# QCLogic_Rev_A_Sht2_WiFi.net
KiCad netlist of a schematic drawn in Altium Designer
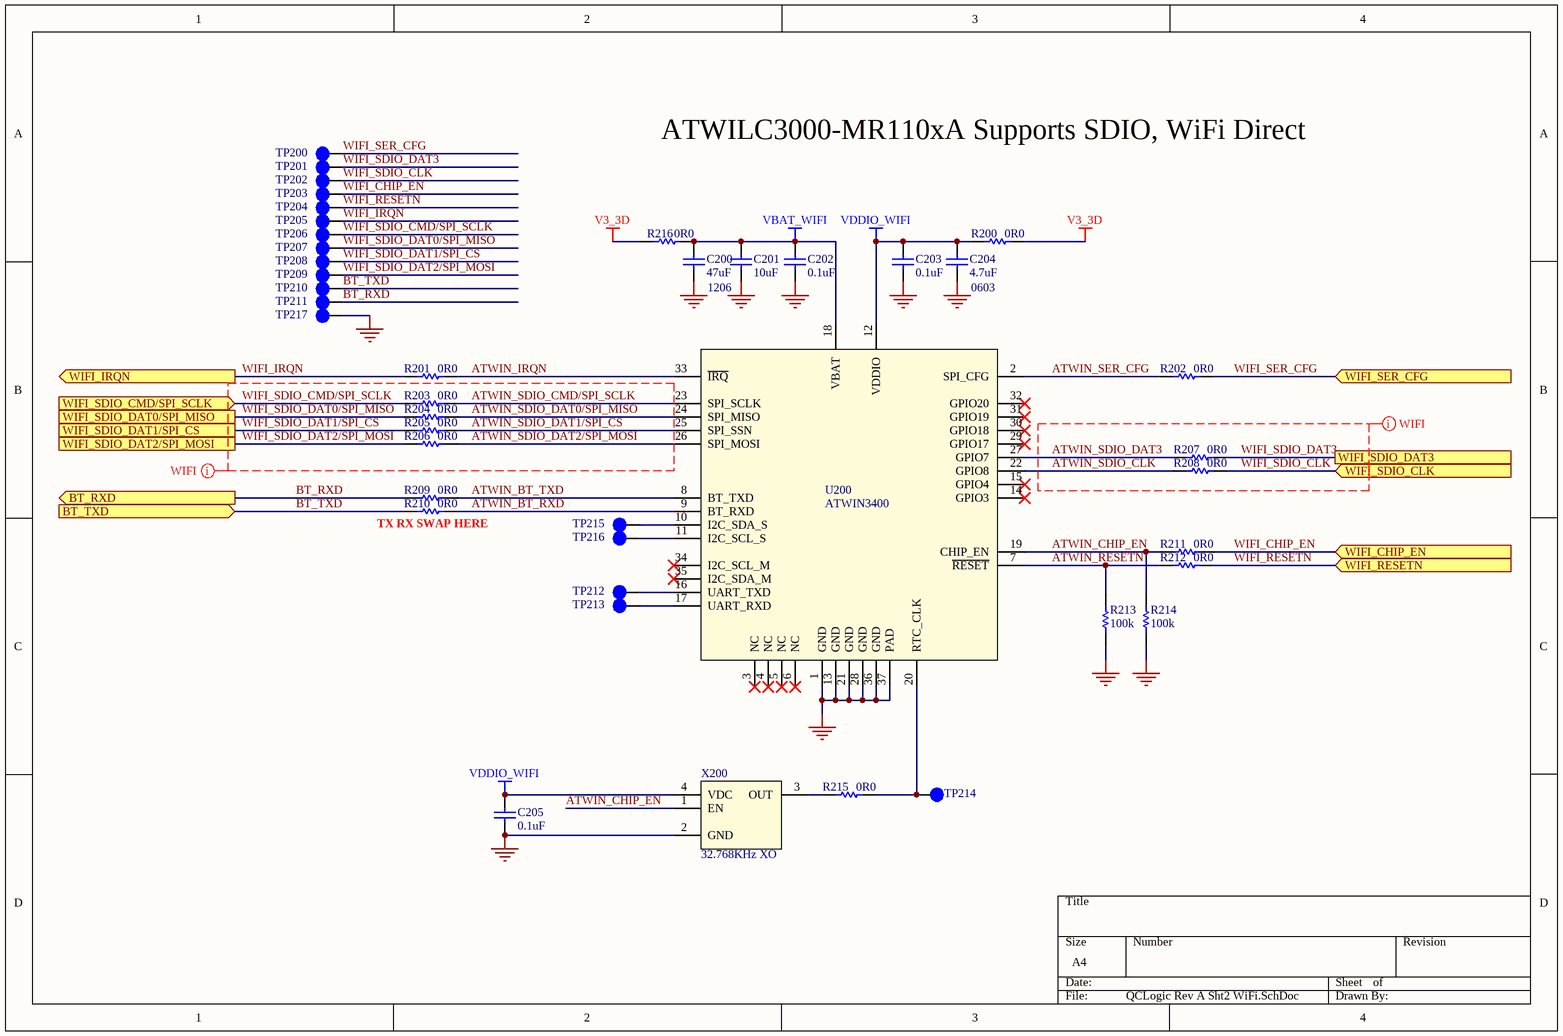
[diagram p0: QCLogic Rev A Sht2 WiFi.SchDoc]

(export (version "E")
  (design (tool "Eeschema 10.0.6"))
  (components
    (comp (ref "C200")
      (value "47uF")
      (footprint "SMD CAP 1206")
      (description "CAP CER 47UF 10V X5R 1206")
      (fields
        (field (name "2. MANUFACTURER PART NUMBER") "CL31A476MPHNNNE")
        (field (name "4. PACKAGE") "1206")
      )
      (libsource (lib "SBCLib") (part "CAP MLCC SMD"))
    )
    (comp (ref "C201")
      (value "10uF")
      (footprint "SMD CAP 0805")
      (description "CAP CER 10UF 25V X5R 0805")
      (fields (field (name "2. MANUFACTURER PART NUMBER") "TMK212BBJ106KG-T"))
      (libsource (lib "SBCLib") (part "CAP MLCC SMD"))
    )
    (comp (ref "C202")
      (value "0.1uF")
      (footprint "SMD CAP 0402")
      (description "CAP CER 0.1UF 25V X7R 0402")
      (fields (field (name "2. MANUFACTURER PART NUMBER") "CC0402KRX7R8BB104"))
      (libsource (lib "SBCLib") (part "CAP MLCC SMD"))
    )
    (comp (ref "C203")
      (value "0.1uF")
      (footprint "SMD CAP 0402")
      (description "CAP CER 0.1UF 25V X7R 0402")
      (fields (field (name "2. MANUFACTURER PART NUMBER") "CC0402KRX7R8BB104"))
      (libsource (lib "SBCLib") (part "CAP MLCC SMD"))
    )
    (comp (ref "C204")
      (value "4.7uF")
      (footprint "SMD CAP 0603")
      (description "CAP CER 4.7UF 16V X7S 0603")
      (fields
        (field (name "2. MANUFACTURER PART NUMBER") "GRM188C71C475KE21D")
        (field (name "4. PACKAGE") "0603")
      )
      (libsource (lib "SBCLib") (part "CAP MLCC SMD"))
    )
    (comp (ref "C205")
      (value "0.1uF")
      (footprint "SMD CAP 0402")
      (description "CAP CER 0.1UF 25V X7R 0402")
      (fields (field (name "2. MANUFACTURER PART NUMBER") "CC0402KRX7R8BB104"))
      (libsource (lib "SBCLib") (part "CAP MLCC SMD"))
    )
    (comp (ref "R200")
      (value "0R0")
      (footprint "SMD RES 0402")
      (description "RES SMD 0 OHM JUMPER 1/16W 0402")
      (fields (field (name "2. MANUFACTURER PART NUMBER") "RC0402FR-070RL"))
      (libsource (lib "SBCLib") (part "RES SMD"))
    )
    (comp (ref "R201")
      (value "0R0")
      (footprint "SMD RES 0402")
      (description "RES SMD 0 OHM JUMPER 1/16W 0402")
      (fields (field (name "2. MANUFACTURER PART NUMBER") "RC0402FR-070RL"))
      (libsource (lib "SBCLib") (part "RES SMD"))
    )
    (comp (ref "R202")
      (value "0R0")
      (footprint "SMD RES 0402")
      (description "RES SMD 0 OHM JUMPER 1/16W 0402")
      (fields (field (name "2. MANUFACTURER PART NUMBER") "RC0402FR-070RL"))
      (libsource (lib "SBCLib") (part "RES SMD"))
    )
    (comp (ref "R203")
      (value "0R0")
      (footprint "SMD RES 0402")
      (description "RES SMD 0 OHM JUMPER 1/16W 0402")
      (fields (field (name "2. MANUFACTURER PART NUMBER") "RC0402FR-070RL"))
      (libsource (lib "SBCLib") (part "RES SMD"))
    )
    (comp (ref "R204")
      (value "0R0")
      (footprint "SMD RES 0402")
      (description "RES SMD 0 OHM JUMPER 1/16W 0402")
      (fields (field (name "2. MANUFACTURER PART NUMBER") "RC0402FR-070RL"))
      (libsource (lib "SBCLib") (part "RES SMD"))
    )
    (comp (ref "R205")
      (value "0R0")
      (footprint "SMD RES 0402")
      (description "RES SMD 0 OHM JUMPER 1/16W 0402")
      (fields (field (name "2. MANUFACTURER PART NUMBER") "RC0402FR-070RL"))
      (libsource (lib "SBCLib") (part "RES SMD"))
    )
    (comp (ref "R206")
      (value "0R0")
      (footprint "SMD RES 0402")
      (description "RES SMD 0 OHM JUMPER 1/16W 0402")
      (fields (field (name "2. MANUFACTURER PART NUMBER") "RC0402FR-070RL"))
      (libsource (lib "SBCLib") (part "RES SMD"))
    )
    (comp (ref "R207")
      (value "0R0")
      (footprint "SMD RES 0402")
      (description "RES SMD 0 OHM JUMPER 1/16W 0402")
      (fields (field (name "2. MANUFACTURER PART NUMBER") "RC0402FR-070RL"))
      (libsource (lib "SBCLib") (part "RES SMD"))
    )
    (comp (ref "R208")
      (value "0R0")
      (footprint "SMD RES 0402")
      (description "RES SMD 0 OHM JUMPER 1/16W 0402")
      (fields (field (name "2. MANUFACTURER PART NUMBER") "RC0402FR-070RL"))
      (libsource (lib "SBCLib") (part "RES SMD"))
    )
    (comp (ref "R209")
      (value "0R0")
      (footprint "SMD RES 0402")
      (description "RES SMD 0 OHM JUMPER 1/16W 0402")
      (fields (field (name "2. MANUFACTURER PART NUMBER") "RC0402FR-070RL"))
      (libsource (lib "SBCLib") (part "RES SMD"))
    )
    (comp (ref "R210")
      (value "0R0")
      (footprint "SMD RES 0402")
      (description "RES SMD 0 OHM JUMPER 1/16W 0402")
      (fields (field (name "2. MANUFACTURER PART NUMBER") "RC0402FR-070RL"))
      (libsource (lib "SBCLib") (part "RES SMD"))
    )
    (comp (ref "R211")
      (value "0R0")
      (footprint "SMD RES 0402")
      (description "RES SMD 0 OHM JUMPER 1/16W 0402")
      (fields (field (name "2. MANUFACTURER PART NUMBER") "RC0402FR-070RL"))
      (libsource (lib "SBCLib") (part "RES SMD"))
    )
    (comp (ref "R212")
      (value "0R0")
      (footprint "SMD RES 0402")
      (description "RES SMD 0 OHM JUMPER 1/16W 0402")
      (fields (field (name "2. MANUFACTURER PART NUMBER") "RC0402FR-070RL"))
      (libsource (lib "SBCLib") (part "RES SMD"))
    )
    (comp (ref "R213")
      (value "100k")
      (footprint "SMD RES 0402")
      (description "RES SMD 100K OHM 1% 1/16W 0402")
      (fields (field (name "2. MANUFACTURER PART NUMBER") "RC0402FR-07100KL"))
      (libsource (lib "SBCLib") (part "RES SMD"))
    )
    (comp (ref "R214")
      (value "100k")
      (footprint "SMD RES 0402")
      (description "RES SMD 100K OHM 1% 1/16W 0402")
      (fields (field (name "2. MANUFACTURER PART NUMBER") "RC0402FR-07100KL"))
      (libsource (lib "SBCLib") (part "RES SMD"))
    )
    (comp (ref "R215")
      (value "0R0")
      (footprint "SMD RES 0402")
      (description "RES SMD 0 OHM JUMPER 1/16W 0402")
      (fields (field (name "2. MANUFACTURER PART NUMBER") "RC0402FR-070RL"))
      (libsource (lib "SBCLib") (part "RES SMD"))
    )
    (comp (ref "R216")
      (value "0R0")
      (footprint "SMD RES 0402")
      (description "RES SMD 0 OHM JUMPER 1/16W 0402")
      (fields (field (name "2. MANUFACTURER PART NUMBER") "RC0402FR-070RL"))
      (libsource (lib "SBCLib") (part "RES SMD"))
    )
    (comp (ref "TP200")
      (value "TESTPOINT SMD")
      (footprint "TESTPOINT 0.5mm DIA")
      (description "TESTPOINT SMD PAD")
      (libsource (lib "SBCLib") (part "TESTPOINT PAD"))
    )
    (comp (ref "TP201")
      (value "TESTPOINT SMD")
      (footprint "TESTPOINT 0.5mm DIA")
      (description "TESTPOINT SMD PAD")
      (libsource (lib "SBCLib") (part "TESTPOINT PAD"))
    )
    (comp (ref "TP202")
      (value "TESTPOINT SMD")
      (footprint "TESTPOINT 0.5mm DIA")
      (description "TESTPOINT SMD PAD")
      (libsource (lib "SBCLib") (part "TESTPOINT PAD"))
    )
    (comp (ref "TP203")
      (value "TESTPOINT SMD")
      (footprint "TESTPOINT 0.5mm DIA")
      (description "TESTPOINT SMD PAD")
      (libsource (lib "SBCLib") (part "TESTPOINT PAD"))
    )
    (comp (ref "TP204")
      (value "TESTPOINT SMD")
      (footprint "TESTPOINT 0.5mm DIA")
      (description "TESTPOINT SMD PAD")
      (libsource (lib "SBCLib") (part "TESTPOINT PAD"))
    )
    (comp (ref "TP205")
      (value "TESTPOINT SMD")
      (footprint "TESTPOINT 0.5mm DIA")
      (description "TESTPOINT SMD PAD")
      (libsource (lib "SBCLib") (part "TESTPOINT PAD"))
    )
    (comp (ref "TP206")
      (value "TESTPOINT SMD")
      (footprint "TESTPOINT 0.5mm DIA")
      (description "TESTPOINT SMD PAD")
      (libsource (lib "SBCLib") (part "TESTPOINT PAD"))
    )
    (comp (ref "TP207")
      (value "TESTPOINT SMD")
      (footprint "TESTPOINT 0.5mm DIA")
      (description "TESTPOINT SMD PAD")
      (libsource (lib "SBCLib") (part "TESTPOINT PAD"))
    )
    (comp (ref "TP208")
      (value "TESTPOINT SMD")
      (footprint "TESTPOINT 0.5mm DIA")
      (description "TESTPOINT SMD PAD")
      (libsource (lib "SBCLib") (part "TESTPOINT PAD"))
    )
    (comp (ref "TP209")
      (value "TESTPOINT SMD")
      (footprint "TESTPOINT 0.5mm DIA")
      (description "TESTPOINT SMD PAD")
      (libsource (lib "SBCLib") (part "TESTPOINT PAD"))
    )
    (comp (ref "TP210")
      (value "TESTPOINT SMD")
      (footprint "TESTPOINT 0.5mm DIA")
      (description "TESTPOINT SMD PAD")
      (libsource (lib "SBCLib") (part "TESTPOINT PAD"))
    )
    (comp (ref "TP211")
      (value "TESTPOINT SMD")
      (footprint "TESTPOINT 0.5mm DIA")
      (description "TESTPOINT SMD PAD")
      (libsource (lib "SBCLib") (part "TESTPOINT PAD"))
    )
    (comp (ref "TP212")
      (value "TESTPOINT SMD")
      (footprint "TESTPOINT 0.5mm DIA")
      (description "TESTPOINT SMD PAD")
      (libsource (lib "SBCLib") (part "TESTPOINT PAD"))
    )
    (comp (ref "TP213")
      (value "TESTPOINT SMD")
      (footprint "TESTPOINT 0.5mm DIA")
      (description "TESTPOINT SMD PAD")
      (libsource (lib "SBCLib") (part "TESTPOINT PAD"))
    )
    (comp (ref "TP214")
      (value "TESTPOINT SMD")
      (footprint "TESTPOINT 0.5mm DIA")
      (description "TESTPOINT SMD PAD")
      (libsource (lib "SBCLib") (part "TESTPOINT PAD"))
    )
    (comp (ref "TP215")
      (value "TESTPOINT SMD")
      (footprint "TESTPOINT 0.5mm DIA")
      (description "TESTPOINT SMD PAD")
      (libsource (lib "SBCLib") (part "TESTPOINT PAD"))
    )
    (comp (ref "TP216")
      (value "TESTPOINT SMD")
      (footprint "TESTPOINT 0.5mm DIA")
      (description "TESTPOINT SMD PAD")
      (libsource (lib "SBCLib") (part "TESTPOINT PAD"))
    )
    (comp (ref "TP217")
      (value "TESTPOINT SMD")
      (footprint "TESTPOINT 1mm DIA")
      (description "TESTPOINT SMD PAD")
      (libsource (lib "SBCLib") (part "TESTPOINT PAD"))
    )
    (comp (ref "U200")
      (value "ATWIN3400")
      (footprint "ATWINC3400-MR210CA")
      (fields (field (name "2. MANUFACTURER PART NUMBER") "ATWINC3400-MR210CA131-T"))
      (libsource (lib "SBCLib") (part "MODULE WIFI 802_11BGN CHIP SMD"))
    )
    (comp (ref "X200")
      (value "32.768KHz XO")
      (footprint "XTAL OSC 32.768K CMOS")
      (description "OSC XO 32.768KHZ HCMOS SMD")
      (fields (field (name "2. MANUFACTURER PART NUMBER") "O 0,032768-JO32-G-1V3-1-T1-LF"))
      (libsource (lib "SBCLib") (part "OSC XO 32.768KHZ HCMOS SMD"))
    )
  )
  (nets
    (net (code "1") (name "/ATWIN_BT_RXD") (class "Default")
      (node (ref "R210") (pin "2") (pinfunction "2_2") (pintype "passive"))
      (node (ref "U200") (pin "9") (pinfunction "BT_RXD_9") (pintype "passive"))
    )
    (net (code "2") (name "/ATWIN_BT_TXD") (class "Default")
      (node (ref "R209") (pin "2") (pinfunction "2_2") (pintype "passive"))
      (node (ref "U200") (pin "8") (pinfunction "BT_TXD_8") (pintype "passive"))
    )
    (net (code "3") (name "/ATWIN_CHIP_EN") (class "Default")
      (node (ref "R211") (pin "1") (pinfunction "1_1") (pintype "passive"))
      (node (ref "R214") (pin "1") (pinfunction "1_1") (pintype "passive"))
      (node (ref "U200") (pin "19") (pinfunction "CHIP_EN_19") (pintype "passive"))
      (node (ref "X200") (pin "1") (pinfunction "EN_1") (pintype "passive"))
    )
    (net (code "4") (name "/ATWIN_IRQN") (class "Default")
      (node (ref "R201") (pin "2") (pinfunction "2_2") (pintype "passive"))
      (node (ref "U200") (pin "33") (pinfunction "~{IRQ}_33") (pintype "passive"))
    )
    (net (code "5") (name "/ATWIN_RESETN") (class "Default")
      (node (ref "R212") (pin "1") (pinfunction "1_1") (pintype "passive"))
      (node (ref "R213") (pin "1") (pinfunction "1_1") (pintype "passive"))
      (node (ref "U200") (pin "7") (pinfunction "~{RESET}_7") (pintype "passive"))
    )
    (net (code "6") (name "/ATWIN_SDIO_CLK") (class "Default")
      (node (ref "R208") (pin "1") (pinfunction "1_1") (pintype "passive"))
      (node (ref "U200") (pin "22") (pinfunction "GPIO8_22") (pintype "passive"))
    )
    (net (code "7") (name "/ATWIN_SDIO_CMD{slash}SPI_SCLK") (class "Default")
      (node (ref "R203") (pin "2") (pinfunction "2_2") (pintype "passive"))
      (node (ref "U200") (pin "23") (pinfunction "SPI_SCLK_23") (pintype "passive"))
    )
    (net (code "8") (name "/ATWIN_SDIO_DAT0{slash}SPI_MISO") (class "Default")
      (node (ref "R204") (pin "2") (pinfunction "2_2") (pintype "passive"))
      (node (ref "U200") (pin "24") (pinfunction "SPI_MISO_24") (pintype "passive"))
    )
    (net (code "9") (name "/ATWIN_SDIO_DAT1{slash}SPI_CS") (class "Default")
      (node (ref "R205") (pin "2") (pinfunction "2_2") (pintype "passive"))
      (node (ref "U200") (pin "25") (pinfunction "SPI_SSN_25") (pintype "passive"))
    )
    (net (code "10") (name "/ATWIN_SDIO_DAT2{slash}SPI_MOSI") (class "Default")
      (node (ref "R206") (pin "2") (pinfunction "2_2") (pintype "passive"))
      (node (ref "U200") (pin "26") (pinfunction "SPI_MOSI_26") (pintype "passive"))
    )
    (net (code "11") (name "/ATWIN_SDIO_DAT3") (class "Default")
      (node (ref "R207") (pin "1") (pinfunction "1_1") (pintype "passive"))
      (node (ref "U200") (pin "27") (pinfunction "GPIO7_27") (pintype "passive"))
    )
    (net (code "12") (name "/ATWIN_SER_CFG") (class "Default")
      (node (ref "R202") (pin "1") (pinfunction "1_1") (pintype "passive"))
      (node (ref "U200") (pin "2") (pinfunction "SPI_CFG_2") (pintype "passive"))
    )
    (net (code "13") (name "/BT_RXD") (class "Default")
      (node (ref "R209") (pin "1") (pinfunction "1_1") (pintype "passive"))
      (node (ref "TP211") (pin "1") (pinfunction "1_1") (pintype "passive"))
    )
    (net (code "14") (name "/BT_TXD") (class "Default")
      (node (ref "R210") (pin "1") (pinfunction "1_1") (pintype "passive"))
      (node (ref "TP210") (pin "1") (pinfunction "1_1") (pintype "passive"))
    )
    (net (code "15") (name "/WIFI_CHIP_EN") (class "Default")
      (node (ref "R211") (pin "2") (pinfunction "2_2") (pintype "passive"))
      (node (ref "TP203") (pin "1") (pinfunction "1_1") (pintype "passive"))
    )
    (net (code "16") (name "/WIFI_IRQN") (class "Default")
      (node (ref "R201") (pin "1") (pinfunction "1_1") (pintype "passive"))
      (node (ref "TP205") (pin "1") (pinfunction "1_1") (pintype "passive"))
    )
    (net (code "17") (name "/WIFI_RESETN") (class "Default")
      (node (ref "R212") (pin "2") (pinfunction "2_2") (pintype "passive"))
      (node (ref "TP204") (pin "1") (pinfunction "1_1") (pintype "passive"))
    )
    (net (code "18") (name "/WIFI_SDIO_CLK") (class "Default")
      (node (ref "R208") (pin "2") (pinfunction "2_2") (pintype "passive"))
      (node (ref "TP202") (pin "1") (pinfunction "1_1") (pintype "passive"))
    )
    (net (code "19") (name "/WIFI_SDIO_CMD{slash}SPI_SCLK") (class "Default")
      (node (ref "R203") (pin "1") (pinfunction "1_1") (pintype "passive"))
      (node (ref "TP206") (pin "1") (pinfunction "1_1") (pintype "passive"))
    )
    (net (code "20") (name "/WIFI_SDIO_DAT0{slash}SPI_MISO") (class "Default")
      (node (ref "R204") (pin "1") (pinfunction "1_1") (pintype "passive"))
      (node (ref "TP207") (pin "1") (pinfunction "1_1") (pintype "passive"))
    )
    (net (code "21") (name "/WIFI_SDIO_DAT1{slash}SPI_CS") (class "Default")
      (node (ref "R205") (pin "1") (pinfunction "1_1") (pintype "passive"))
      (node (ref "TP208") (pin "1") (pinfunction "1_1") (pintype "passive"))
    )
    (net (code "22") (name "/WIFI_SDIO_DAT2{slash}SPI_MOSI") (class "Default")
      (node (ref "R206") (pin "1") (pinfunction "1_1") (pintype "passive"))
      (node (ref "TP209") (pin "1") (pinfunction "1_1") (pintype "passive"))
    )
    (net (code "23") (name "/WIFI_SDIO_DAT3") (class "Default")
      (node (ref "R207") (pin "2") (pinfunction "2_2") (pintype "passive"))
      (node (ref "TP201") (pin "1") (pinfunction "1_1") (pintype "passive"))
    )
    (net (code "24") (name "/WIFI_SER_CFG") (class "Default")
      (node (ref "R202") (pin "2") (pinfunction "2_2") (pintype "passive"))
      (node (ref "TP200") (pin "1") (pinfunction "1_1") (pintype "passive"))
    )
    (net (code "25") (name "GND") (class "Default")
      (node (ref "C200") (pin "2") (pinfunction "2_2") (pintype "passive"))
      (node (ref "C201") (pin "2") (pinfunction "2_2") (pintype "passive"))
      (node (ref "C202") (pin "1") (pinfunction "1_1") (pintype "passive"))
      (node (ref "C203") (pin "1") (pinfunction "1_1") (pintype "passive"))
      (node (ref "C204") (pin "2") (pinfunction "2_2") (pintype "passive"))
      (node (ref "C205") (pin "1") (pinfunction "1_1") (pintype "passive"))
      (node (ref "R213") (pin "2") (pinfunction "2_2") (pintype "passive"))
      (node (ref "R214") (pin "2") (pinfunction "2_2") (pintype "passive"))
      (node (ref "TP217") (pin "1") (pinfunction "1_1") (pintype "passive"))
      (node (ref "U200") (pin "1") (pinfunction "GND_1") (pintype "passive"))
      (node (ref "U200") (pin "13") (pinfunction "GND_13") (pintype "passive"))
      (node (ref "U200") (pin "21") (pinfunction "GND_21") (pintype "passive"))
      (node (ref "U200") (pin "28") (pinfunction "GND_28") (pintype "passive"))
      (node (ref "U200") (pin "36") (pinfunction "GND_36") (pintype "passive"))
      (node (ref "U200") (pin "37") (pinfunction "PAD_37") (pintype "passive"))
      (node (ref "X200") (pin "2") (pinfunction "GND_2") (pintype "passive"))
    )
    (net (code "26") (name "Net-(U200-I2C_SCL_S)") (class "Default")
      (node (ref "TP216") (pin "1") (pinfunction "1_1") (pintype "passive"))
      (node (ref "U200") (pin "11") (pinfunction "I2C_SCL_S_11") (pintype "passive"))
    )
    (net (code "27") (name "Net-(U200-I2C_SDA_S)") (class "Default")
      (node (ref "TP215") (pin "1") (pinfunction "1_1") (pintype "passive"))
      (node (ref "U200") (pin "10") (pinfunction "I2C_SDA_S_10") (pintype "passive"))
    )
    (net (code "28") (name "Net-(U200-RTC_CLK)") (class "Default")
      (node (ref "R215") (pin "2") (pinfunction "2_2") (pintype "passive"))
      (node (ref "TP214") (pin "1") (pinfunction "1_1") (pintype "passive"))
      (node (ref "U200") (pin "20") (pinfunction "RTC_CLK_20") (pintype "passive"))
    )
    (net (code "29") (name "Net-(U200-UART_RXD)") (class "Default")
      (node (ref "TP213") (pin "1") (pinfunction "1_1") (pintype "passive"))
      (node (ref "U200") (pin "17") (pinfunction "UART_RXD_17") (pintype "passive"))
    )
    (net (code "30") (name "Net-(U200-UART_TXD)") (class "Default")
      (node (ref "TP212") (pin "1") (pinfunction "1_1") (pintype "passive"))
      (node (ref "U200") (pin "16") (pinfunction "UART_TXD_16") (pintype "passive"))
    )
    (net (code "31") (name "Net-(X200-OUT)") (class "Default")
      (node (ref "R215") (pin "1") (pinfunction "1_1") (pintype "passive"))
      (node (ref "X200") (pin "3") (pinfunction "OUT_3") (pintype "passive"))
    )
    (net (code "32") (name "V3_3D") (class "Default")
      (node (ref "R200") (pin "2") (pinfunction "2_2") (pintype "passive"))
      (node (ref "R216") (pin "1") (pinfunction "1_1") (pintype "passive"))
    )
    (net (code "33") (name "VBAT_WIFI") (class "Default")
      (node (ref "C200") (pin "1") (pinfunction "1_1") (pintype "passive"))
      (node (ref "C201") (pin "1") (pinfunction "1_1") (pintype "passive"))
      (node (ref "C202") (pin "2") (pinfunction "2_2") (pintype "passive"))
      (node (ref "R216") (pin "2") (pinfunction "2_2") (pintype "passive"))
      (node (ref "U200") (pin "18") (pinfunction "VBAT_18") (pintype "passive"))
    )
    (net (code "34") (name "VDDIO_WIFI") (class "Default")
      (node (ref "C203") (pin "2") (pinfunction "2_2") (pintype "passive"))
      (node (ref "C204") (pin "1") (pinfunction "1_1") (pintype "passive"))
      (node (ref "C205") (pin "2") (pinfunction "2_2") (pintype "passive"))
      (node (ref "R200") (pin "1") (pinfunction "1_1") (pintype "passive"))
      (node (ref "U200") (pin "12") (pinfunction "VDDIO_12") (pintype "passive"))
      (node (ref "X200") (pin "4") (pinfunction "VDC_4") (pintype "passive"))
    )
    (net (code "35") (name "unconnected-(U200-GPIO3-Pad14)") (class "Default")
      (node (ref "U200") (pin "14") (pinfunction "GPIO3_14") (pintype "passive+no_connect"))
    )
    (net (code "36") (name "unconnected-(U200-GPIO4-Pad15)") (class "Default")
      (node (ref "U200") (pin "15") (pinfunction "GPIO4_15") (pintype "passive+no_connect"))
    )
    (net (code "37") (name "unconnected-(U200-GPIO17-Pad29)") (class "Default")
      (node (ref "U200") (pin "29") (pinfunction "GPIO17_29") (pintype "passive+no_connect"))
    )
    (net (code "38") (name "unconnected-(U200-GPIO18-Pad30)") (class "Default")
      (node (ref "U200") (pin "30") (pinfunction "GPIO18_30") (pintype "passive+no_connect"))
    )
    (net (code "39") (name "unconnected-(U200-GPIO19-Pad31)") (class "Default")
      (node (ref "U200") (pin "31") (pinfunction "GPIO19_31") (pintype "passive+no_connect"))
    )
    (net (code "40") (name "unconnected-(U200-GPIO20-Pad32)") (class "Default")
      (node (ref "U200") (pin "32") (pinfunction "GPIO20_32") (pintype "passive+no_connect"))
    )
    (net (code "41") (name "unconnected-(U200-I2C_SCL_M-Pad34)") (class "Default")
      (node (ref "U200") (pin "34") (pinfunction "I2C_SCL_M_34") (pintype "passive+no_connect"))
    )
    (net (code "42") (name "unconnected-(U200-I2C_SDA_M-Pad35)") (class "Default")
      (node (ref "U200") (pin "35") (pinfunction "I2C_SDA_M_35") (pintype "passive+no_connect"))
    )
    (net (code "43") (name "unconnected-(U200-NC-Pad3)") (class "Default")
      (node (ref "U200") (pin "3") (pinfunction "NC_3") (pintype "passive+no_connect"))
    )
    (net (code "44") (name "unconnected-(U200-NC-Pad4)") (class "Default")
      (node (ref "U200") (pin "4") (pinfunction "NC_4") (pintype "passive+no_connect"))
    )
    (net (code "45") (name "unconnected-(U200-NC-Pad5)") (class "Default")
      (node (ref "U200") (pin "5") (pinfunction "NC_5") (pintype "passive+no_connect"))
    )
    (net (code "46") (name "unconnected-(U200-NC-Pad6)") (class "Default")
      (node (ref "U200") (pin "6") (pinfunction "NC_6") (pintype "passive+no_connect"))
    )
  )
)
